# Power.net
KiCad netlist of a schematic drawn in Altium Designer
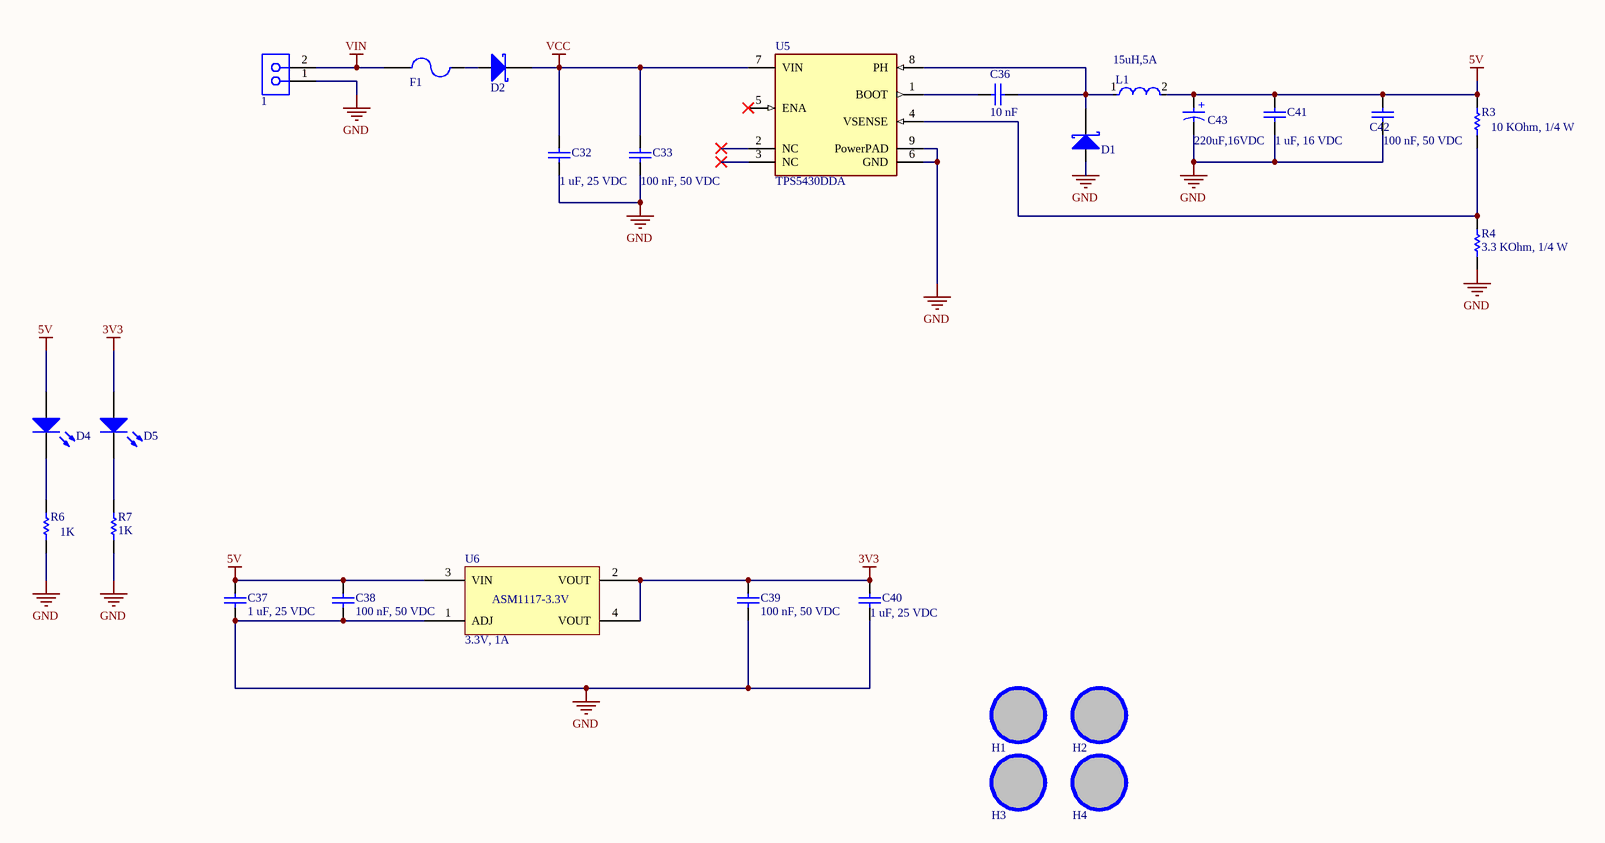
[diagram p0: Power.SchDoc]

(export (version "E")
  (design (tool "Eeschema 10.0.6"))
  (components
    (comp (ref "1")
      (value "4A, 300V")
      (footprint "691418420002")
      (description "WR-TBL Series 4184 45° Entry, THT, pitch 7.62mm, 2p")
      (fields
        (field (name "MANUFACTURER PART NUMBER") "691418420002")
        (field (name "MANUFACTURER") "Wurth Elektronik")
      )
      (libsource (lib "Altium_Terminal_Block") (part "691418420002"))
    )
    (comp (ref "C32")
      (value "1 uF, 25 VDC")
      (footprint "CAP_0603")
      (description "CAP, size 0603, 1 uF, 25 VDC")
      (fields (field (name "TOLERANCE") "+/-10%"))
      (libsource (lib "Altium_Ceramic_Cap") (part "0106031051025"))
    )
    (comp (ref "C33")
      (value "100 nF, 50 VDC")
      (footprint "CAP_0603")
      (description "CAP, size 0603, 100 nF, 50 VDC")
      (fields (field (name "TOLERANCE") "+/-10%"))
      (libsource (lib "Altium_Ceramic_Cap") (part "0106031041050"))
    )
    (comp (ref "C36")
      (value "10 nF")
      (footprint "CAP_0603")
      (description "CAP, size 0603, 10 nF, 50 VDC")
      (fields (field (name "TOLERANCE") "+/-5%"))
      (libsource (lib "Altium_Ceramic_Cap") (part "0106031000550"))
    )
    (comp (ref "C37")
      (value "1 uF, 25 VDC")
      (footprint "CAP_0603")
      (description "CAP, size 0603, 1 uF, 25 VDC")
      (fields (field (name "TOLERANCE") "+/-10%"))
      (libsource (lib "Altium_Ceramic_Cap") (part "0106031051025"))
    )
    (comp (ref "C38")
      (value "100 nF, 50 VDC")
      (footprint "CAP_0603")
      (description "CAP, size 0603, 100 nF, 50 VDC")
      (fields (field (name "TOLERANCE") "+/-10%"))
      (libsource (lib "Altium_Ceramic_Cap") (part "0106031041050"))
    )
    (comp (ref "C39")
      (value "100 nF, 50 VDC")
      (footprint "CAP_0603")
      (description "CAP, size 0603, 100 nF, 50 VDC")
      (fields (field (name "TOLERANCE") "+/-10%"))
      (libsource (lib "Altium_Ceramic_Cap") (part "0106031041050"))
    )
    (comp (ref "C40")
      (value "1 uF, 25 VDC")
      (footprint "CAP_0603")
      (description "CAP, size 0603, 1 uF, 25 VDC")
      (fields (field (name "TOLERANCE") "+/-10%"))
      (libsource (lib "Altium_Ceramic_Cap") (part "0106031051025"))
    )
    (comp (ref "C41")
      (value "1 uF, 16 VDC")
      (footprint "CAP_0603")
      (description "CAP, size 0603, 1 uF, 16 VDC")
      (fields (field (name "TOLERANCE") "+/-10%"))
      (libsource (lib "Altium_Ceramic_Cap") (part "0106031051016"))
    )
    (comp (ref "C42")
      (value "100 nF, 50 VDC")
      (footprint "CAP_0603")
      (description "CAP, size 0603, 100 nF, 50 VDC")
      (fields (field (name "TOLERANCE") "+/-10%"))
      (libsource (lib "Altium_Ceramic_Cap") (part "0106031041050"))
    )
    (comp (ref "C43")
      (value "220uF,16VDC")
      (footprint "WCAP-ASLI_D6.3H7.7")
      (description "V-Chip, D6.3 x H7.7mm, 220uF, 16V")
      (fields (field (name "MANUFACTURER") "Wurth Elektronik"))
      (libsource (lib "Altium_Alutinum_Cap") (part "865080345012"))
    )
    (comp (ref "D1")
      (value "D Schottky")
      (footprint "SS34")
      (description "Schottky Diode")
      (fields (field (name "PUBLISHER") "Altium Limited"))
      (libsource (lib "Board_C24") (part "D Schottky"))
    )
    (comp (ref "D2")
      (value "D Schottky")
      (footprint "SS34")
      (description "Schottky Diode")
      (fields (field (name "PUBLISHER") "Altium Limited"))
      (libsource (lib "Board_C24") (part "D Schottky"))
    )
    (comp (ref "D4")
      (value "LED SMD")
      (footprint "LED_0805_Blue")
      (description "LED")
      (libsource (lib "Board_C24") (part "LED SMD"))
    )
    (comp (ref "D5")
      (value "LED SMD")
      (footprint "LED_0805_Blue")
      (description "LED")
      (libsource (lib "Board_C24") (part "LED SMD"))
    )
    (comp (ref "F1") (value "Fuse") (footprint "FUSE SMD") (libsource (lib "Board_C24") (part "Fuse")))
    (comp (ref "H1")
      (value "Hole")
      (footprint "LO KHOAN 3MM")
      (description "Hole 3mm")
      (libsource (lib "Board_C24") (part "Hole"))
    )
    (comp (ref "H2")
      (value "Hole")
      (footprint "LO KHOAN 3MM")
      (description "Hole 3mm")
      (libsource (lib "Board_C24") (part "Hole"))
    )
    (comp (ref "H3")
      (value "Hole")
      (footprint "LO KHOAN 3MM")
      (description "Hole 3mm")
      (libsource (lib "Board_C24") (part "Hole"))
    )
    (comp (ref "H4")
      (value "Hole")
      (footprint "LO KHOAN 3MM")
      (description "Hole 3mm")
      (libsource (lib "Board_C24") (part "Hole"))
    )
    (comp (ref "L1")
      (value "15uH,5A")
      (footprint "FP-SRR1260-MFG")
      (description "FIXED IND 15UH 5A 27 MOHM SMD")
      (fields (field (name "TOLERANCE") "20%"))
      (libsource (lib "Altium Content Vault") (part "725321dda6339637d4d059423bc1c3c"))
    )
    (comp (ref "R3")
      (value "10 KOhm, 1/4 W")
      (footprint "resistor_0603")
      (description "RES, size 0603, 10 KOhm, 1/4 W")
      (libsource (lib "Altium_Resistor") (part "0006031031"))
    )
    (comp (ref "R4")
      (value "3.3 KOhm, 1/4 W")
      (footprint "resistor_0603")
      (description "RES, size 0603, 3.3 KOhm, 1/4 W")
      (libsource (lib "Altium_Resistor") (part "0006033321"))
    )
    (comp (ref "R6")
      (value "1K")
      (footprint "resistor_0603")
      (description "RES, size 0603, 21 KOhm, 1/4 W")
      (libsource (lib "Altium_Resistor") (part "0006032135"))
    )
    (comp (ref "R7")
      (value "1K")
      (footprint "resistor_0603")
      (description "RES, size 0603, 1 KOhm, 1/4 W")
      (libsource (lib "Altium_Resistor") (part "0006031025"))
    )
    (comp (ref "U5")
      (value "TPS5430DDA")
      (footprint "FP-DDA0008J-MFG")
      (description "IC REG BUCK ADJUSTABLE 3A 8SOPWR")
      (fields
        (field (name "MANUFACTURER") "Texas Instruments")
        (field (name "OCTOPART") "https://octopart.com/tps5430dda-texas+instruments-589977")
      )
      (libsource (lib "Altium Content Vault") (part "98da629940cea6febc5630bb55159f3"))
    )
    (comp (ref "U6")
      (value "3.3V, 1A")
      (footprint "AMS1117-3.3V SOT223")
      (description "AMS1117-3.3V, OUT 3.3V 1A.")
      (fields (field (name "MANUFACTURER") "AMS"))
      (libsource (lib "Altium_Power_Supply_IC") (part "AMS1117-3.3V"))
    )
  )
  (nets
    (net (code "1") (name "3V3") (class "Default")
      (node (ref "C39") (pin "2") (pinfunction "2_2") (pintype "passive"))
      (node (ref "C40") (pin "2") (pinfunction "2_2") (pintype "passive"))
      (node (ref "D5") (pin "1") (pinfunction "A_1") (pintype "passive"))
      (node (ref "U6") (pin "2") (pinfunction "VOUT_2") (pintype "passive"))
      (node (ref "U6") (pin "4") (pinfunction "VOUT_4") (pintype "power_in"))
    )
    (net (code "2") (name "5V") (class "Default")
      (node (ref "C37") (pin "2") (pinfunction "2_2") (pintype "passive"))
      (node (ref "C38") (pin "2") (pinfunction "2_2") (pintype "passive"))
      (node (ref "C41") (pin "2") (pinfunction "2_2") (pintype "passive"))
      (node (ref "C42") (pin "2") (pinfunction "2_2") (pintype "passive"))
      (node (ref "C43") (pin "1") (pinfunction "P_1") (pintype "passive"))
      (node (ref "D4") (pin "1") (pinfunction "A_1") (pintype "passive"))
      (node (ref "L1") (pin "2") (pinfunction "2_2") (pintype "passive"))
      (node (ref "R3") (pin "2") (pinfunction "2_2") (pintype "passive"))
      (node (ref "U6") (pin "3") (pinfunction "VIN_3") (pintype "passive"))
    )
    (net (code "3") (name "GND") (class "Default")
      (node (ref "1") (pin "1") (pinfunction "1_1") (pintype "passive"))
      (node (ref "C32") (pin "1") (pinfunction "1_1") (pintype "passive"))
      (node (ref "C33") (pin "1") (pinfunction "1_1") (pintype "passive"))
      (node (ref "C37") (pin "1") (pinfunction "1_1") (pintype "passive"))
      (node (ref "C38") (pin "1") (pinfunction "1_1") (pintype "passive"))
      (node (ref "C39") (pin "1") (pinfunction "1_1") (pintype "passive"))
      (node (ref "C40") (pin "1") (pinfunction "1_1") (pintype "passive"))
      (node (ref "C41") (pin "1") (pinfunction "1_1") (pintype "passive"))
      (node (ref "C42") (pin "1") (pinfunction "1_1") (pintype "passive"))
      (node (ref "C43") (pin "2") (pinfunction "N_2") (pintype "passive"))
      (node (ref "D1") (pin "1") (pinfunction "A_1") (pintype "passive"))
      (node (ref "R4") (pin "1") (pinfunction "1_1") (pintype "passive"))
      (node (ref "R6") (pin "1") (pinfunction "1_1") (pintype "passive"))
      (node (ref "R7") (pin "1") (pinfunction "1_1") (pintype "passive"))
      (node (ref "U5") (pin "6") (pinfunction "GND_6") (pintype "power_in"))
      (node (ref "U5") (pin "9") (pinfunction "PowerPAD_9") (pintype "power_in"))
      (node (ref "U6") (pin "1") (pinfunction "ADJ_1") (pintype "power_in"))
    )
    (net (code "4") (name "Net-(D1-K)") (class "Default")
      (node (ref "C36") (pin "2") (pinfunction "2_2") (pintype "passive"))
      (node (ref "D1") (pin "2") (pinfunction "K_2") (pintype "passive"))
      (node (ref "L1") (pin "1") (pinfunction "1_1") (pintype "passive"))
      (node (ref "U5") (pin "8") (pinfunction "PH_8") (pintype "input"))
    )
    (net (code "5") (name "Net-(D2-A)") (class "Default")
      (node (ref "D2") (pin "1") (pinfunction "A_1") (pintype "passive"))
      (node (ref "F1") (pin "2") (pinfunction "2_2") (pintype "passive"))
    )
    (net (code "6") (name "Net-(D4-K)") (class "Default")
      (node (ref "D4") (pin "2") (pinfunction "K_2") (pintype "passive"))
      (node (ref "R6") (pin "2") (pinfunction "2_2") (pintype "passive"))
    )
    (net (code "7") (name "Net-(D5-K)") (class "Default")
      (node (ref "D5") (pin "2") (pinfunction "K_2") (pintype "passive"))
      (node (ref "R7") (pin "2") (pinfunction "2_2") (pintype "passive"))
    )
    (net (code "8") (name "Net-(U5-BOOT)") (class "Default")
      (node (ref "C36") (pin "1") (pinfunction "1_1") (pintype "passive"))
      (node (ref "U5") (pin "1") (pinfunction "BOOT_1") (pintype "output"))
    )
    (net (code "9") (name "Net-(U5-VSENSE)") (class "Default")
      (node (ref "R3") (pin "1") (pinfunction "1_1") (pintype "passive"))
      (node (ref "R4") (pin "2") (pinfunction "2_2") (pintype "passive"))
      (node (ref "U5") (pin "4") (pinfunction "VSENSE_4") (pintype "input"))
    )
    (net (code "10") (name "VCC") (class "Default")
      (node (ref "C32") (pin "2") (pinfunction "2_2") (pintype "passive"))
      (node (ref "C33") (pin "2") (pinfunction "2_2") (pintype "passive"))
      (node (ref "D2") (pin "2") (pinfunction "K_2") (pintype "passive"))
      (node (ref "U5") (pin "7") (pinfunction "VIN_7") (pintype "power_in"))
    )
    (net (code "11") (name "VIN") (class "Default")
      (node (ref "1") (pin "2") (pinfunction "2_2") (pintype "passive"))
      (node (ref "F1") (pin "1") (pinfunction "1_1") (pintype "passive"))
    )
    (net (code "12") (name "unconnected-(H1-Pad1)") (class "Default")
      (node (ref "H1") (pin "1") (pinfunction "1_1") (pintype "passive"))
    )
    (net (code "13") (name "unconnected-(H2-Pad1)") (class "Default")
      (node (ref "H2") (pin "1") (pinfunction "1_1") (pintype "passive"))
    )
    (net (code "14") (name "unconnected-(H3-Pad1)") (class "Default")
      (node (ref "H3") (pin "1") (pinfunction "1_1") (pintype "passive"))
    )
    (net (code "15") (name "unconnected-(H4-Pad1)") (class "Default")
      (node (ref "H4") (pin "1") (pinfunction "1_1") (pintype "passive"))
    )
    (net (code "16") (name "unconnected-(U5-ENA-Pad5)") (class "Default")
      (node (ref "U5") (pin "5") (pinfunction "ENA_5") (pintype "input+no_connect"))
    )
    (net (code "17") (name "unconnected-(U5-NC-Pad2)") (class "Default")
      (node (ref "U5") (pin "2") (pinfunction "NC_2") (pintype "passive+no_connect"))
    )
    (net (code "18") (name "unconnected-(U5-NC-Pad3)") (class "Default")
      (node (ref "U5") (pin "3") (pinfunction "NC_3") (pintype "passive+no_connect"))
    )
  )
)
